# DB10011_CANConnector.net
KiCad netlist of a schematic drawn in Altium Designer
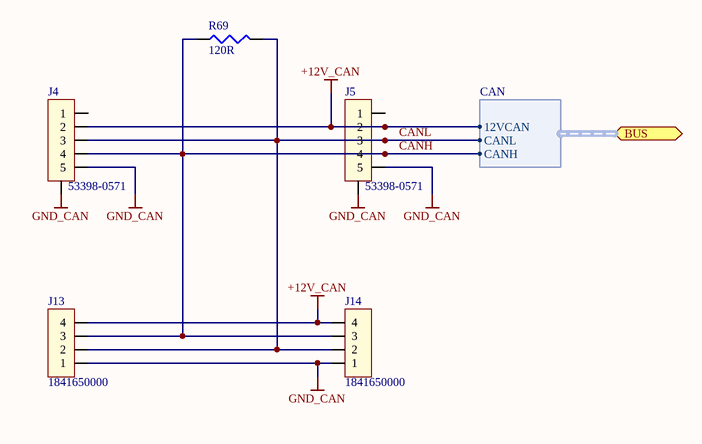
[diagram p0: DB10011_CANConnector.SchDoc]

(export (version "E")
  (design (tool "Eeschema 10.0.6"))
  (components
    (comp (ref "J4")
      (value "53398-0571")
      (footprint "53398-0571")
      (description "PicoBlade 53398 Series, 5Pin, Right Angle")
      (libsource (lib "AR_Connectors") (part "53398-0571"))
    )
    (comp (ref "J5")
      (value "53398-0571")
      (footprint "53398-0571")
      (description "PicoBlade 53398 Series, 5Pin, Right Angle")
      (libsource (lib "AR_Connectors") (part "53398-0571"))
    )
    (comp (ref "J13")
      (value "1841650000")
      (footprint "1841650000")
      (description "SL-SMT Header, 3.5 mm, 4 Ways, 15 A, 320 V")
      (libsource (lib "AR_Connectors") (part "1841650000"))
    )
    (comp (ref "J14")
      (value "1841650000")
      (footprint "1841650000")
      (description "SL-SMT Header, 3.5 mm, 4 Ways, 15 A, 320 V")
      (libsource (lib "") (part "1841650000_1"))
    )
    (comp (ref "R69")
      (value "120R")
      (footprint "0805")
      (description "Resistor, 0R, 0.1%, 0.1W, 150V, 200PPM, 0805")
      (libsource (lib "AR_Resistors_SMD") (part "0/0805/0100W/150V"))
    )
  )
  (nets
    (net (code "2") (name "+12V_CAN") (class "Default")
      (node (ref "J13") (pin "4") (pinfunction "4_4") (pintype "passive"))
      (node (ref "J14") (pin "4") (pinfunction "4_4") (pintype "passive"))
      (node (ref "J4") (pin "2") (pinfunction "2_2") (pintype "passive"))
      (node (ref "J5") (pin "2") (pinfunction "2_2") (pintype "passive"))
    )
    (net (code "3") (name "/CANH") (class "Default")
      (node (ref "J13") (pin "3") (pinfunction "3_3") (pintype "passive"))
      (node (ref "J14") (pin "3") (pinfunction "3_3") (pintype "passive"))
      (node (ref "J4") (pin "4") (pinfunction "4_4") (pintype "passive"))
      (node (ref "J5") (pin "4") (pinfunction "4_4") (pintype "passive"))
      (node (ref "R69") (pin "2") (pinfunction "2_2") (pintype "passive"))
    )
    (net (code "4") (name "/CANL") (class "Default")
      (node (ref "J13") (pin "2") (pinfunction "2_2") (pintype "passive"))
      (node (ref "J14") (pin "2") (pinfunction "2_2") (pintype "passive"))
      (node (ref "J4") (pin "3") (pinfunction "3_3") (pintype "passive"))
      (node (ref "J5") (pin "3") (pinfunction "3_3") (pintype "passive"))
      (node (ref "R69") (pin "1") (pinfunction "1_1") (pintype "passive"))
    )
    (net (code "6") (name "GND_CAN") (class "Default")
      (node (ref "J13") (pin "1") (pinfunction "1_1") (pintype "passive"))
      (node (ref "J14") (pin "1") (pinfunction "1_1") (pintype "passive"))
      (node (ref "J4") (pin "0") (pinfunction "SHLD_0") (pintype "passive"))
      (node (ref "J4") (pin "5") (pinfunction "5_5") (pintype "passive"))
      (node (ref "J5") (pin "0") (pinfunction "SHLD_0") (pintype "passive"))
      (node (ref "J5") (pin "5") (pinfunction "5_5") (pintype "passive"))
    )
    (net (code "7") (name "unconnected-(J4-Pad1)") (class "Default")
      (node (ref "J4") (pin "1") (pinfunction "1_1") (pintype "passive"))
    )
    (net (code "8") (name "unconnected-(J5-Pad1)") (class "Default")
      (node (ref "J5") (pin "1") (pinfunction "1_1") (pintype "passive"))
    )
  )
)
